# SPI_LCD_Backpack.net
KiCad netlist of a schematic drawn in EAGLE
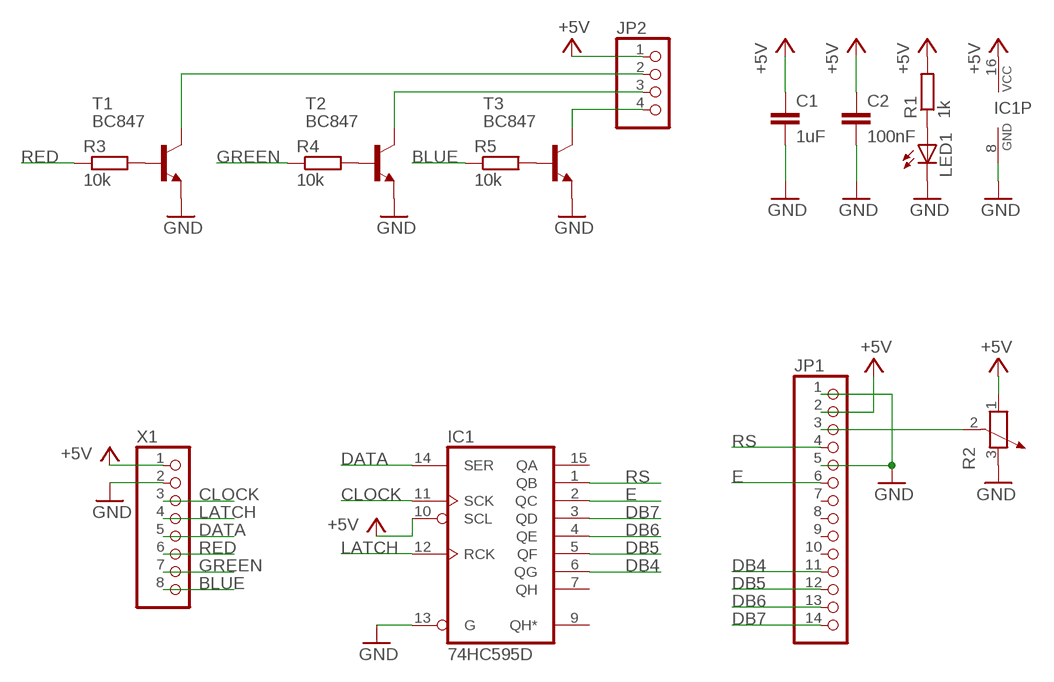
[diagram p0: schematic, sheet 1]

(export (version "E")
  (design (tool "Eeschema 10.0.6"))
  (components
    (comp (ref "C1")
      (value "1uF")
      (footprint "eagle-import:C0805K")
      (libsource (lib "eagle-import") (part "C-EUC0805K"))
    )
    (comp (ref "C2")
      (value "100nF")
      (footprint "eagle-import:C0805K")
      (libsource (lib "eagle-import") (part "C-EUC0805K"))
    )
    (comp (ref "IC1")
      (value "74HC595D")
      (footprint "eagle-import:SO16")
      (libsource (lib "eagle-import") (part "74595DHC"))
    )
    (comp (ref "JP1")
      (value "PINHD-1X14")
      (footprint "eagle-import:1X14")
      (libsource (lib "eagle-import") (part "PINHD-1X14"))
    )
    (comp (ref "JP2")
      (value "PINHD-1X4")
      (footprint "eagle-import:1X04")
      (libsource (lib "eagle-import") (part "PINHD-1X4"))
    )
    (comp (ref "LED1")
      (value "LED3MM")
      (footprint "eagle-import:LED3MM")
      (libsource (lib "eagle-import") (part "LED3MM"))
    )
    (comp (ref "R1")
      (value "1k")
      (footprint "eagle-import:R0805")
      (libsource (lib "eagle-import") (part "R-EU_0805"))
    )
    (comp (ref "R2")
      (value "POTENTIOMETER_3386F")
      (footprint "eagle-import:3386F")
      (libsource (lib "eagle-import") (part "POTENTIOMETER_3386F"))
    )
    (comp (ref "R3")
      (value "10k")
      (footprint "eagle-import:R0805")
      (libsource (lib "eagle-import") (part "R-EU_0805"))
    )
    (comp (ref "R4")
      (value "10k")
      (footprint "eagle-import:R0805")
      (libsource (lib "eagle-import") (part "R-EU_0805"))
    )
    (comp (ref "R5")
      (value "10k")
      (footprint "eagle-import:R0805")
      (libsource (lib "eagle-import") (part "R-EU_0805"))
    )
    (comp (ref "T1")
      (value "BC847")
      (footprint "eagle-import:SOT23")
      (libsource (lib "eagle-import") (part "BC847"))
    )
    (comp (ref "T2")
      (value "BC847")
      (footprint "eagle-import:SOT23")
      (libsource (lib "eagle-import") (part "BC847"))
    )
    (comp (ref "T3")
      (value "BC847")
      (footprint "eagle-import:SOT23")
      (libsource (lib "eagle-import") (part "BC847"))
    )
    (comp (ref "X1")
      (value "22-23-2081")
      (footprint "eagle-import:22-23-2081")
      (fields (field (name "MF") "MOLEX"))
      (libsource (lib "eagle-import") (part "22-23-2081"))
    )
  )
  (nets
    (net (code "1") (name "+5V") (class "Default")
      (node (ref "C1") (pin "1") (pinfunction "1_1") (pintype "passive"))
      (node (ref "C2") (pin "1") (pinfunction "1_1") (pintype "passive"))
      (node (ref "IC1") (pin "10") (pinfunction "SCL_10") (pintype "input"))
      (node (ref "IC1") (pin "16") (pinfunction "VCC_16") (pintype "power_in"))
      (node (ref "JP1") (pin "2") (pinfunction "2_2") (pintype "passive"))
      (node (ref "JP2") (pin "1") (pinfunction "1_1") (pintype "passive"))
      (node (ref "R1") (pin "2") (pinfunction "2_2") (pintype "passive"))
      (node (ref "R2") (pin "1") (pinfunction "1_1") (pintype "passive"))
      (node (ref "X1") (pin "1") (pinfunction "1_1") (pintype "passive"))
    )
    (net (code "2") (name "/BLUE") (class "Default")
      (node (ref "R5") (pin "1") (pinfunction "1_1") (pintype "passive"))
      (node (ref "X1") (pin "8") (pinfunction "8_8") (pintype "passive"))
    )
    (net (code "3") (name "/CLOCK") (class "Default")
      (node (ref "IC1") (pin "11") (pinfunction "SCK_11") (pintype "input"))
      (node (ref "X1") (pin "3") (pinfunction "3_3") (pintype "passive"))
    )
    (net (code "4") (name "/DATA") (class "Default")
      (node (ref "IC1") (pin "14") (pinfunction "SER_14") (pintype "input"))
      (node (ref "X1") (pin "5") (pinfunction "5_5") (pintype "passive"))
    )
    (net (code "5") (name "/DB4") (class "Default")
      (node (ref "IC1") (pin "6") (pinfunction "QG_6") (pintype "tri_state"))
      (node (ref "JP1") (pin "11") (pinfunction "11_11") (pintype "passive"))
    )
    (net (code "6") (name "/DB5") (class "Default")
      (node (ref "IC1") (pin "5") (pinfunction "QF_5") (pintype "tri_state"))
      (node (ref "JP1") (pin "12") (pinfunction "12_12") (pintype "passive"))
    )
    (net (code "7") (name "/DB6") (class "Default")
      (node (ref "IC1") (pin "4") (pinfunction "QE_4") (pintype "tri_state"))
      (node (ref "JP1") (pin "13") (pinfunction "13_13") (pintype "passive"))
    )
    (net (code "8") (name "/DB7") (class "Default")
      (node (ref "IC1") (pin "3") (pinfunction "QD_3") (pintype "tri_state"))
      (node (ref "JP1") (pin "14") (pinfunction "14_14") (pintype "passive"))
    )
    (net (code "9") (name "/E") (class "Default")
      (node (ref "IC1") (pin "2") (pinfunction "QC_2") (pintype "tri_state"))
      (node (ref "JP1") (pin "6") (pinfunction "6_6") (pintype "passive"))
    )
    (net (code "10") (name "/GREEN") (class "Default")
      (node (ref "R4") (pin "1") (pinfunction "1_1") (pintype "passive"))
      (node (ref "X1") (pin "7") (pinfunction "7_7") (pintype "passive"))
    )
    (net (code "11") (name "/LATCH") (class "Default")
      (node (ref "IC1") (pin "12") (pinfunction "RCK_12") (pintype "input"))
      (node (ref "X1") (pin "4") (pinfunction "4_4") (pintype "passive"))
    )
    (net (code "12") (name "/RED") (class "Default")
      (node (ref "R3") (pin "1") (pinfunction "1_1") (pintype "passive"))
      (node (ref "X1") (pin "6") (pinfunction "6_6") (pintype "passive"))
    )
    (net (code "13") (name "/RS") (class "Default")
      (node (ref "IC1") (pin "1") (pinfunction "QB_1") (pintype "tri_state"))
      (node (ref "JP1") (pin "4") (pinfunction "4_4") (pintype "passive"))
    )
    (net (code "14") (name "GND") (class "Default")
      (node (ref "C1") (pin "2") (pinfunction "2_2") (pintype "passive"))
      (node (ref "C2") (pin "2") (pinfunction "2_2") (pintype "passive"))
      (node (ref "IC1") (pin "13") (pinfunction "G_13") (pintype "input"))
      (node (ref "IC1") (pin "8") (pinfunction "GND_8") (pintype "power_in"))
      (node (ref "JP1") (pin "1") (pinfunction "1_1") (pintype "passive"))
      (node (ref "JP1") (pin "5") (pinfunction "5_5") (pintype "passive"))
      (node (ref "LED1") (pin "K") (pinfunction "C_K") (pintype "passive"))
      (node (ref "R2") (pin "3") (pinfunction "2_3") (pintype "passive"))
      (node (ref "T1") (pin "2") (pinfunction "E_2") (pintype "passive"))
      (node (ref "T2") (pin "2") (pinfunction "E_2") (pintype "passive"))
      (node (ref "T3") (pin "2") (pinfunction "E_2") (pintype "passive"))
      (node (ref "X1") (pin "2") (pinfunction "2_2") (pintype "passive"))
    )
    (net (code "15") (name "Net-(LED1-PadA)") (class "Default")
      (node (ref "LED1") (pin "A") (pinfunction "A_A") (pintype "passive"))
      (node (ref "R1") (pin "1") (pinfunction "1_1") (pintype "passive"))
    )
    (net (code "16") (name "Net-(R2-3)") (class "Default")
      (node (ref "JP1") (pin "3") (pinfunction "3_3") (pintype "passive"))
      (node (ref "R2") (pin "2") (pinfunction "3_2") (pintype "passive"))
    )
    (net (code "17") (name "Net-(T1-B)") (class "Default")
      (node (ref "R3") (pin "2") (pinfunction "2_2") (pintype "passive"))
      (node (ref "T1") (pin "1") (pinfunction "B_1") (pintype "passive"))
    )
    (net (code "18") (name "Net-(T1-C)") (class "Default")
      (node (ref "JP2") (pin "2") (pinfunction "2_2") (pintype "passive"))
      (node (ref "T1") (pin "3") (pinfunction "C_3") (pintype "passive"))
    )
    (net (code "19") (name "Net-(T2-B)") (class "Default")
      (node (ref "R4") (pin "2") (pinfunction "2_2") (pintype "passive"))
      (node (ref "T2") (pin "1") (pinfunction "B_1") (pintype "passive"))
    )
    (net (code "20") (name "Net-(T2-C)") (class "Default")
      (node (ref "JP2") (pin "3") (pinfunction "3_3") (pintype "passive"))
      (node (ref "T2") (pin "3") (pinfunction "C_3") (pintype "passive"))
    )
    (net (code "21") (name "Net-(T3-B)") (class "Default")
      (node (ref "R5") (pin "2") (pinfunction "2_2") (pintype "passive"))
      (node (ref "T3") (pin "1") (pinfunction "B_1") (pintype "passive"))
    )
    (net (code "22") (name "Net-(T3-C)") (class "Default")
      (node (ref "JP2") (pin "4") (pinfunction "4_4") (pintype "passive"))
      (node (ref "T3") (pin "3") (pinfunction "C_3") (pintype "passive"))
    )
    (net (code "23") (name "unconnected-(IC1A-QA-Pad15)") (class "Default")
      (node (ref "IC1") (pin "15") (pinfunction "QA_15") (pintype "tri_state"))
    )
    (net (code "24") (name "unconnected-(IC1A-QH*-Pad9)") (class "Default")
      (node (ref "IC1") (pin "9") (pinfunction "QH*_9") (pintype "tri_state"))
    )
    (net (code "25") (name "unconnected-(IC1A-QH-Pad7)") (class "Default")
      (node (ref "IC1") (pin "7") (pinfunction "QH_7") (pintype "tri_state"))
    )
    (net (code "26") (name "unconnected-(JP1-Pad7)") (class "Default")
      (node (ref "JP1") (pin "7") (pinfunction "7_7") (pintype "passive"))
    )
    (net (code "27") (name "unconnected-(JP1-Pad8)") (class "Default")
      (node (ref "JP1") (pin "8") (pinfunction "8_8") (pintype "passive"))
    )
    (net (code "28") (name "unconnected-(JP1-Pad9)") (class "Default")
      (node (ref "JP1") (pin "9") (pinfunction "9_9") (pintype "passive"))
    )
    (net (code "29") (name "unconnected-(JP1-Pad10)") (class "Default")
      (node (ref "JP1") (pin "10") (pinfunction "10_10") (pintype "passive"))
    )
  )
)
